# audio_wattmeter.net
KiCad netlist of a schematic drawn in EAGLE
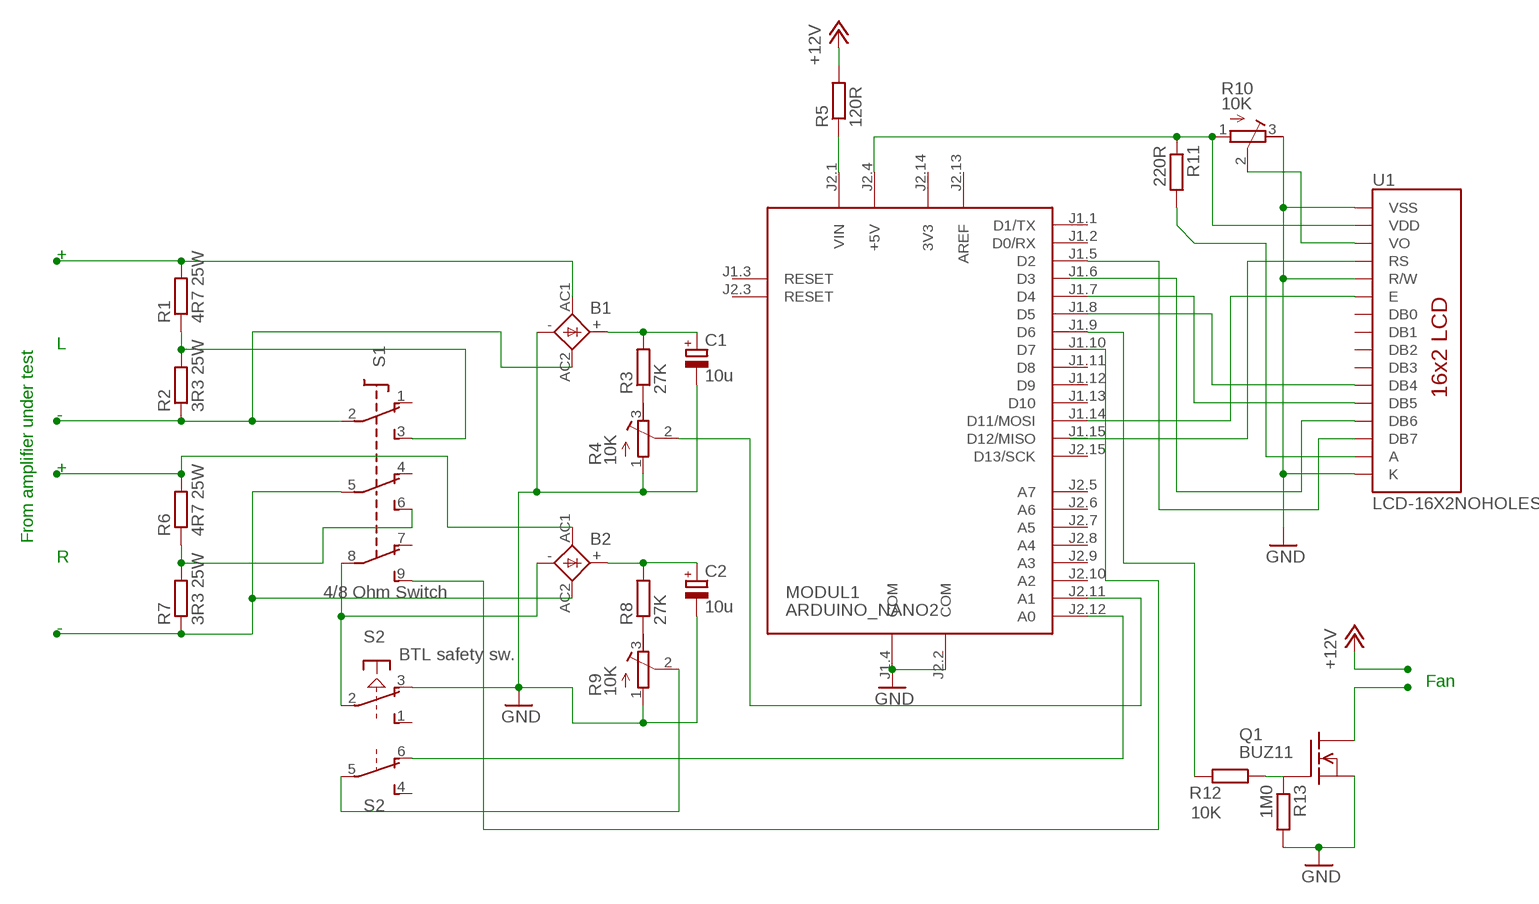
[diagram p0: schematic, sheet 1]

(export (version "E")
  (design (tool "Eeschema 10.0.6"))
  (components
    (comp (ref "B1")
      (value "FB32")
      (footprint "eagle-import:FB32")
      (libsource (lib "eagle-import") (part "FB32"))
    )
    (comp (ref "B2")
      (value "FB32")
      (footprint "eagle-import:FB32")
      (libsource (lib "eagle-import") (part "FB32"))
    )
    (comp (ref "C1")
      (value "10u")
      (footprint "eagle-import:139CLL-3W")
      (libsource (lib "eagle-import") (part "CPOL-EU139CLL-3W"))
    )
    (comp (ref "C2")
      (value "10u")
      (footprint "eagle-import:139CLL-3W")
      (libsource (lib "eagle-import") (part "CPOL-EU139CLL-3W"))
    )
    (comp (ref "MODUL1")
      (value "ARDUINO_NANO2")
      (footprint "eagle-import:ARDUINO_NANO2")
      (libsource (lib "eagle-import") (part "ARDUINO_NANO2"))
    )
    (comp (ref "Q1")
      (value "BUZ11")
      (footprint "eagle-import:TO220")
      (libsource (lib "eagle-import") (part "BUZ11"))
    )
    (comp (ref "R1")
      (value "4R7 25W")
      (footprint "eagle-import:P0613_15")
      (libsource (lib "eagle-import") (part "R-EU_0613/15"))
    )
    (comp (ref "R2")
      (value "3R3 25W")
      (footprint "eagle-import:P0613_15")
      (libsource (lib "eagle-import") (part "R-EU_0613/15"))
    )
    (comp (ref "R3")
      (value "27K")
      (footprint "eagle-import:P0613_15")
      (libsource (lib "eagle-import") (part "R-EU_0613/15"))
    )
    (comp (ref "R4")
      (value "10K")
      (footprint "eagle-import:RTRIM3202")
      (libsource (lib "eagle-import") (part "R-TRIMM3202"))
    )
    (comp (ref "R5")
      (value "120R")
      (footprint "eagle-import:P0613_15")
      (libsource (lib "eagle-import") (part "R-EU_0613/15"))
    )
    (comp (ref "R6")
      (value "4R7 25W")
      (footprint "eagle-import:P0613_15")
      (libsource (lib "eagle-import") (part "R-EU_0613/15"))
    )
    (comp (ref "R7")
      (value "3R3 25W")
      (footprint "eagle-import:P0613_15")
      (libsource (lib "eagle-import") (part "R-EU_0613/15"))
    )
    (comp (ref "R8")
      (value "27K")
      (footprint "eagle-import:P0613_15")
      (libsource (lib "eagle-import") (part "R-EU_0613/15"))
    )
    (comp (ref "R9")
      (value "10K")
      (footprint "eagle-import:RTRIM3202")
      (libsource (lib "eagle-import") (part "R-TRIMM3202"))
    )
    (comp (ref "R10")
      (value "10K")
      (footprint "eagle-import:RTRIM3202")
      (libsource (lib "eagle-import") (part "R-TRIMM3202"))
    )
    (comp (ref "R11")
      (value "220R")
      (footprint "eagle-import:P0613_15")
      (libsource (lib "eagle-import") (part "R-EU_0613/15"))
    )
    (comp (ref "R12")
      (value "10K")
      (footprint "eagle-import:P0613_15")
      (libsource (lib "eagle-import") (part "R-EU_0613/15"))
    )
    (comp (ref "R13")
      (value "1M0")
      (footprint "eagle-import:P0613_15")
      (libsource (lib "eagle-import") (part "R-EU_0613/15"))
    )
    (comp (ref "S1")
      (value "4/8 Ohm Switch")
      (footprint "eagle-import:3PDT")
      (libsource (lib "eagle-import") (part "3PDT"))
    )
    (comp (ref "S2")
      (value "BTL safety sw.")
      (footprint "eagle-import:PVA2R")
      (libsource (lib "eagle-import") (part "PVA2R"))
    )
    (comp (ref "U1")
      (value "LCD-16X2NOHOLES")
      (footprint "eagle-import:LCD-16X2_NOHOLES")
      (libsource (lib "eagle-import") (part "LCD-16X2NOHOLES"))
    )
  )
  (nets
    (net (code "1") (name "+12V") (class "Default")
      (node (ref "R5") (pin "2") (pinfunction "2_2") (pintype "passive"))
    )
    (net (code "2") (name "/3V3") (class "Default")
      (node (ref "MODUL1") (pin "J2.14") (pinfunction "3V3_J2.14") (pintype "power_in"))
    )
    (net (code "3") (name "/AREF") (class "Default")
      (node (ref "MODUL1") (pin "J2.13") (pinfunction "AREF_J2.13") (pintype "power_in"))
    )
    (net (code "4") (name "GND") (class "Default")
      (node (ref "B1") (pin "-") (pinfunction "-_-") (pintype "passive"))
      (node (ref "C1") (pin "-") (pinfunction "-_-") (pintype "passive"))
      (node (ref "C2") (pin "-") (pinfunction "-_-") (pintype "passive"))
      (node (ref "MODUL1") (pin "J1.4") (pinfunction "COM_J1.4") (pintype "power_in"))
      (node (ref "MODUL1") (pin "J2.2") (pinfunction "COM_J2.2") (pintype "power_in"))
      (node (ref "Q1") (pin "3") (pinfunction "S_3") (pintype "passive"))
      (node (ref "R10") (pin "3") (pinfunction "E_3") (pintype "passive"))
      (node (ref "R13") (pin "2") (pinfunction "2_2") (pintype "passive"))
      (node (ref "R4") (pin "1") (pinfunction "A_1") (pintype "passive"))
      (node (ref "R9") (pin "1") (pinfunction "A_1") (pintype "passive"))
      (node (ref "S2") (pin "3") (pinfunction "O_3") (pintype "passive"))
      (node (ref "U1") (pin "1") (pinfunction "VSS_1") (pintype "power_in"))
      (node (ref "U1") (pin "16") (pinfunction "K_16") (pintype "power_in"))
      (node (ref "U1") (pin "5") (pinfunction "R/W_5") (pintype "input"))
    )
    (net (code "5") (name "Net-(B1-Pad+)") (class "Default")
      (node (ref "B1") (pin "+") (pinfunction "+_+") (pintype "passive"))
      (node (ref "C1") (pin "+") (pinfunction "+_+") (pintype "passive"))
      (node (ref "R3") (pin "2") (pinfunction "2_2") (pintype "passive"))
    )
    (net (code "6") (name "Net-(B1-PadAC1)") (class "Default")
      (node (ref "B1") (pin "AC1") (pinfunction "AC1_AC1") (pintype "passive"))
      (node (ref "R1") (pin "2") (pinfunction "2_2") (pintype "passive"))
    )
    (net (code "7") (name "Net-(B2-Pad+)") (class "Default")
      (node (ref "B2") (pin "+") (pinfunction "+_+") (pintype "passive"))
      (node (ref "C2") (pin "+") (pinfunction "+_+") (pintype "passive"))
      (node (ref "R8") (pin "2") (pinfunction "2_2") (pintype "passive"))
    )
    (net (code "8") (name "Net-(B2-PadAC1)") (class "Default")
      (node (ref "B2") (pin "AC1") (pinfunction "AC1_AC1") (pintype "passive"))
      (node (ref "R6") (pin "2") (pinfunction "2_2") (pintype "passive"))
    )
    (net (code "9") (name "Net-(MODUL1-+5V)") (class "Default")
      (node (ref "MODUL1") (pin "J2.4") (pinfunction "+5V_J2.4") (pintype "power_in"))
      (node (ref "R10") (pin "1") (pinfunction "A_1") (pintype "passive"))
      (node (ref "R11") (pin "1") (pinfunction "1_1") (pintype "passive"))
      (node (ref "U1") (pin "2") (pinfunction "VDD_2") (pintype "power_in"))
    )
    (net (code "10") (name "Net-(MODUL1-A0)") (class "Default")
      (node (ref "MODUL1") (pin "J2.12") (pinfunction "A0_J2.12") (pintype "bidirectional"))
      (node (ref "S2") (pin "6") (pinfunction "O_6") (pintype "passive"))
    )
    (net (code "11") (name "Net-(MODUL1-A1)") (class "Default")
      (node (ref "MODUL1") (pin "J2.11") (pinfunction "A1_J2.11") (pintype "bidirectional"))
      (node (ref "R4") (pin "2") (pinfunction "S_2") (pintype "passive"))
    )
    (net (code "12") (name "Net-(MODUL1-D2)") (class "Default")
      (node (ref "MODUL1") (pin "J1.5") (pinfunction "D2_J1.5") (pintype "bidirectional"))
      (node (ref "U1") (pin "14") (pinfunction "DB7_14") (pintype "bidirectional"))
    )
    (net (code "13") (name "Net-(MODUL1-D4)") (class "Default")
      (node (ref "MODUL1") (pin "J1.7") (pinfunction "D4_J1.7") (pintype "bidirectional"))
      (node (ref "U1") (pin "12") (pinfunction "DB5_12") (pintype "bidirectional"))
    )
    (net (code "14") (name "Net-(MODUL1-D5)") (class "Default")
      (node (ref "MODUL1") (pin "J1.8") (pinfunction "D5_J1.8") (pintype "bidirectional"))
      (node (ref "U1") (pin "11") (pinfunction "DB4_11") (pintype "bidirectional"))
    )
    (net (code "15") (name "Net-(MODUL1-D6)") (class "Default")
      (node (ref "MODUL1") (pin "J1.9") (pinfunction "D6_J1.9") (pintype "bidirectional"))
      (node (ref "R12") (pin "2") (pinfunction "2_2") (pintype "passive"))
    )
    (net (code "16") (name "Net-(MODUL1-D7)") (class "Default")
      (node (ref "MODUL1") (pin "J1.10") (pinfunction "D7_J1.10") (pintype "bidirectional"))
      (node (ref "S1") (pin "9") (pinfunction "S3_9") (pintype "passive"))
    )
    (net (code "17") (name "Net-(MODUL1-D11{slash}MOSI)") (class "Default")
      (node (ref "MODUL1") (pin "J1.14") (pinfunction "D11/MOSI_J1.14") (pintype "bidirectional"))
      (node (ref "U1") (pin "6") (pinfunction "E_6") (pintype "input"))
    )
    (net (code "18") (name "Net-(MODUL1-VIN)") (class "Default")
      (node (ref "MODUL1") (pin "J2.1") (pinfunction "VIN_J2.1") (pintype "power_in"))
      (node (ref "R5") (pin "1") (pinfunction "1_1") (pintype "passive"))
    )
    (net (code "19") (name "Net-(Q1-G)") (class "Default")
      (node (ref "Q1") (pin "1") (pinfunction "G_1") (pintype "passive"))
      (node (ref "R12") (pin "1") (pinfunction "1_1") (pintype "passive"))
      (node (ref "R13") (pin "1") (pinfunction "1_1") (pintype "passive"))
    )
    (net (code "20") (name "Net-(R4-E)") (class "Default")
      (node (ref "R3") (pin "1") (pinfunction "1_1") (pintype "passive"))
      (node (ref "R4") (pin "3") (pinfunction "E_3") (pintype "passive"))
    )
    (net (code "21") (name "Net-(R9-E)") (class "Default")
      (node (ref "R8") (pin "1") (pinfunction "1_1") (pintype "passive"))
      (node (ref "R9") (pin "3") (pinfunction "E_3") (pintype "passive"))
    )
    (net (code "22") (name "Net-(R9-S)") (class "Default")
      (node (ref "R9") (pin "2") (pinfunction "S_2") (pintype "passive"))
      (node (ref "S2") (pin "5") (pinfunction "P_5") (pintype "passive"))
    )
    (net (code "23") (name "Net-(R10-S)") (class "Default")
      (node (ref "R10") (pin "2") (pinfunction "S_2") (pintype "passive"))
      (node (ref "U1") (pin "3") (pinfunction "VO_3") (pintype "bidirectional"))
    )
    (net (code "24") (name "Net-(S1-P1)") (class "Default")
      (node (ref "B1") (pin "AC2") (pinfunction "AC2_AC2") (pintype "passive"))
      (node (ref "R2") (pin "1") (pinfunction "1_1") (pintype "passive"))
      (node (ref "S1") (pin "2") (pinfunction "P1_2") (pintype "passive"))
    )
    (net (code "25") (name "Net-(S1-P2)") (class "Default")
      (node (ref "B2") (pin "AC2") (pinfunction "AC2_AC2") (pintype "passive"))
      (node (ref "R7") (pin "1") (pinfunction "1_1") (pintype "passive"))
      (node (ref "S1") (pin "5") (pinfunction "P2_5") (pintype "passive"))
    )
    (net (code "26") (name "Net-(S1-P3)") (class "Default")
      (node (ref "B2") (pin "-") (pinfunction "-_-") (pintype "passive"))
      (node (ref "S1") (pin "8") (pinfunction "P3_8") (pintype "passive"))
      (node (ref "S2") (pin "2") (pinfunction "P_2") (pintype "passive"))
    )
    (net (code "27") (name "Net-(S1-S1)") (class "Default")
      (node (ref "R1") (pin "1") (pinfunction "1_1") (pintype "passive"))
      (node (ref "R2") (pin "2") (pinfunction "2_2") (pintype "passive"))
      (node (ref "S1") (pin "3") (pinfunction "S1_3") (pintype "passive"))
    )
    (net (code "28") (name "Net-(S1-S2)") (class "Default")
      (node (ref "R6") (pin "1") (pinfunction "1_1") (pintype "passive"))
      (node (ref "R7") (pin "2") (pinfunction "2_2") (pintype "passive"))
      (node (ref "S1") (pin "6") (pinfunction "S2_6") (pintype "passive"))
    )
    (net (code "29") (name "Net-(U1-A)") (class "Default")
      (node (ref "R11") (pin "2") (pinfunction "2_2") (pintype "passive"))
      (node (ref "U1") (pin "15") (pinfunction "A_15") (pintype "power_in"))
    )
    (net (code "30") (name "unconnected-(MODUL1-A2-PadJ2.10)") (class "Default")
      (node (ref "MODUL1") (pin "J2.10") (pinfunction "A2_J2.10") (pintype "bidirectional"))
    )
    (net (code "31") (name "unconnected-(MODUL1-A3-PadJ2.9)") (class "Default")
      (node (ref "MODUL1") (pin "J2.9") (pinfunction "A3_J2.9") (pintype "bidirectional"))
    )
    (net (code "32") (name "unconnected-(MODUL1-A4-PadJ2.8)") (class "Default")
      (node (ref "MODUL1") (pin "J2.8") (pinfunction "A4_J2.8") (pintype "bidirectional"))
    )
    (net (code "33") (name "unconnected-(MODUL1-A5-PadJ2.7)") (class "Default")
      (node (ref "MODUL1") (pin "J2.7") (pinfunction "A5_J2.7") (pintype "bidirectional"))
    )
    (net (code "34") (name "unconnected-(MODUL1-A6-PadJ2.6)") (class "Default")
      (node (ref "MODUL1") (pin "J2.6") (pinfunction "A6_J2.6") (pintype "bidirectional"))
    )
    (net (code "35") (name "unconnected-(MODUL1-A7-PadJ2.5)") (class "Default")
      (node (ref "MODUL1") (pin "J2.5") (pinfunction "A7_J2.5") (pintype "bidirectional"))
    )
    (net (code "36") (name "unconnected-(MODUL1-D0{slash}RX-PadJ1.2)") (class "Default")
      (node (ref "MODUL1") (pin "J1.2") (pinfunction "D0/RX_J1.2") (pintype "bidirectional"))
    )
    (net (code "37") (name "unconnected-(MODUL1-D1{slash}TX-PadJ1.1)") (class "Default")
      (node (ref "MODUL1") (pin "J1.1") (pinfunction "D1/TX_J1.1") (pintype "bidirectional"))
    )
    (net (code "38") (name "unconnected-(MODUL1-D3-PadJ1.6)") (class "Default")
      (node (ref "MODUL1") (pin "J1.6") (pinfunction "D3_J1.6") (pintype "bidirectional"))
    )
    (net (code "39") (name "unconnected-(MODUL1-D8-PadJ1.11)") (class "Default")
      (node (ref "MODUL1") (pin "J1.11") (pinfunction "D8_J1.11") (pintype "bidirectional"))
    )
    (net (code "40") (name "unconnected-(MODUL1-D9-PadJ1.12)") (class "Default")
      (node (ref "MODUL1") (pin "J1.12") (pinfunction "D9_J1.12") (pintype "bidirectional"))
    )
    (net (code "41") (name "unconnected-(MODUL1-D10-PadJ1.13)") (class "Default")
      (node (ref "MODUL1") (pin "J1.13") (pinfunction "D10_J1.13") (pintype "bidirectional"))
    )
    (net (code "42") (name "unconnected-(MODUL1-D12{slash}MISO-PadJ1.15)") (class "Default")
      (node (ref "MODUL1") (pin "J1.15") (pinfunction "D12/MISO_J1.15") (pintype "bidirectional"))
    )
    (net (code "43") (name "unconnected-(MODUL1-D13{slash}SCK-PadJ2.15)") (class "Default")
      (node (ref "MODUL1") (pin "J2.15") (pinfunction "D13/SCK_J2.15") (pintype "bidirectional"))
    )
    (net (code "44") (name "unconnected-(MODUL1-RESET-PadJ1.3)") (class "Default")
      (node (ref "MODUL1") (pin "J1.3") (pinfunction "RESET_J1.3") (pintype "bidirectional"))
    )
    (net (code "45") (name "unconnected-(MODUL1-RESET-PadJ2.3)") (class "Default")
      (node (ref "MODUL1") (pin "J2.3") (pinfunction "RESET_J2.3") (pintype "bidirectional"))
    )
    (net (code "46") (name "unconnected-(Q1-D-Pad2)") (class "Default")
      (node (ref "Q1") (pin "2") (pinfunction "D_2") (pintype "passive"))
    )
    (net (code "47") (name "unconnected-(S1-O1-Pad1)") (class "Default")
      (node (ref "S1") (pin "1") (pinfunction "O1_1") (pintype "passive"))
    )
    (net (code "48") (name "unconnected-(S1-O2-Pad4)") (class "Default")
      (node (ref "S1") (pin "4") (pinfunction "O2_4") (pintype "passive"))
    )
    (net (code "49") (name "unconnected-(S1-O3-Pad7)") (class "Default")
      (node (ref "S1") (pin "7") (pinfunction "O3_7") (pintype "passive"))
    )
    (net (code "50") (name "unconnected-(S2A-S-Pad1)") (class "Default")
      (node (ref "S2") (pin "1") (pinfunction "S_1") (pintype "passive"))
    )
    (net (code "51") (name "unconnected-(S2B-S-Pad4)") (class "Default")
      (node (ref "S2") (pin "4") (pinfunction "S_4") (pintype "passive"))
    )
    (net (code "52") (name "unconnected-(U1-DB0-Pad7)") (class "Default")
      (node (ref "U1") (pin "7") (pinfunction "DB0_7") (pintype "bidirectional"))
    )
    (net (code "53") (name "unconnected-(U1-DB1-Pad8)") (class "Default")
      (node (ref "U1") (pin "8") (pinfunction "DB1_8") (pintype "bidirectional"))
    )
    (net (code "54") (name "unconnected-(U1-DB2-Pad9)") (class "Default")
      (node (ref "U1") (pin "9") (pinfunction "DB2_9") (pintype "bidirectional"))
    )
    (net (code "55") (name "unconnected-(U1-DB3-Pad10)") (class "Default")
      (node (ref "U1") (pin "10") (pinfunction "DB3_10") (pintype "bidirectional"))
    )
    (net (code "56") (name "unconnected-(U1-DB6-Pad13)") (class "Default")
      (node (ref "U1") (pin "13") (pinfunction "DB6_13") (pintype "bidirectional"))
    )
    (net (code "57") (name "unconnected-(U1-RS-Pad4)") (class "Default")
      (node (ref "U1") (pin "4") (pinfunction "RS_4") (pintype "input"))
    )
  )
)
